# raspdancer21_1_0.net
KiCad netlist of a schematic drawn in EAGLE
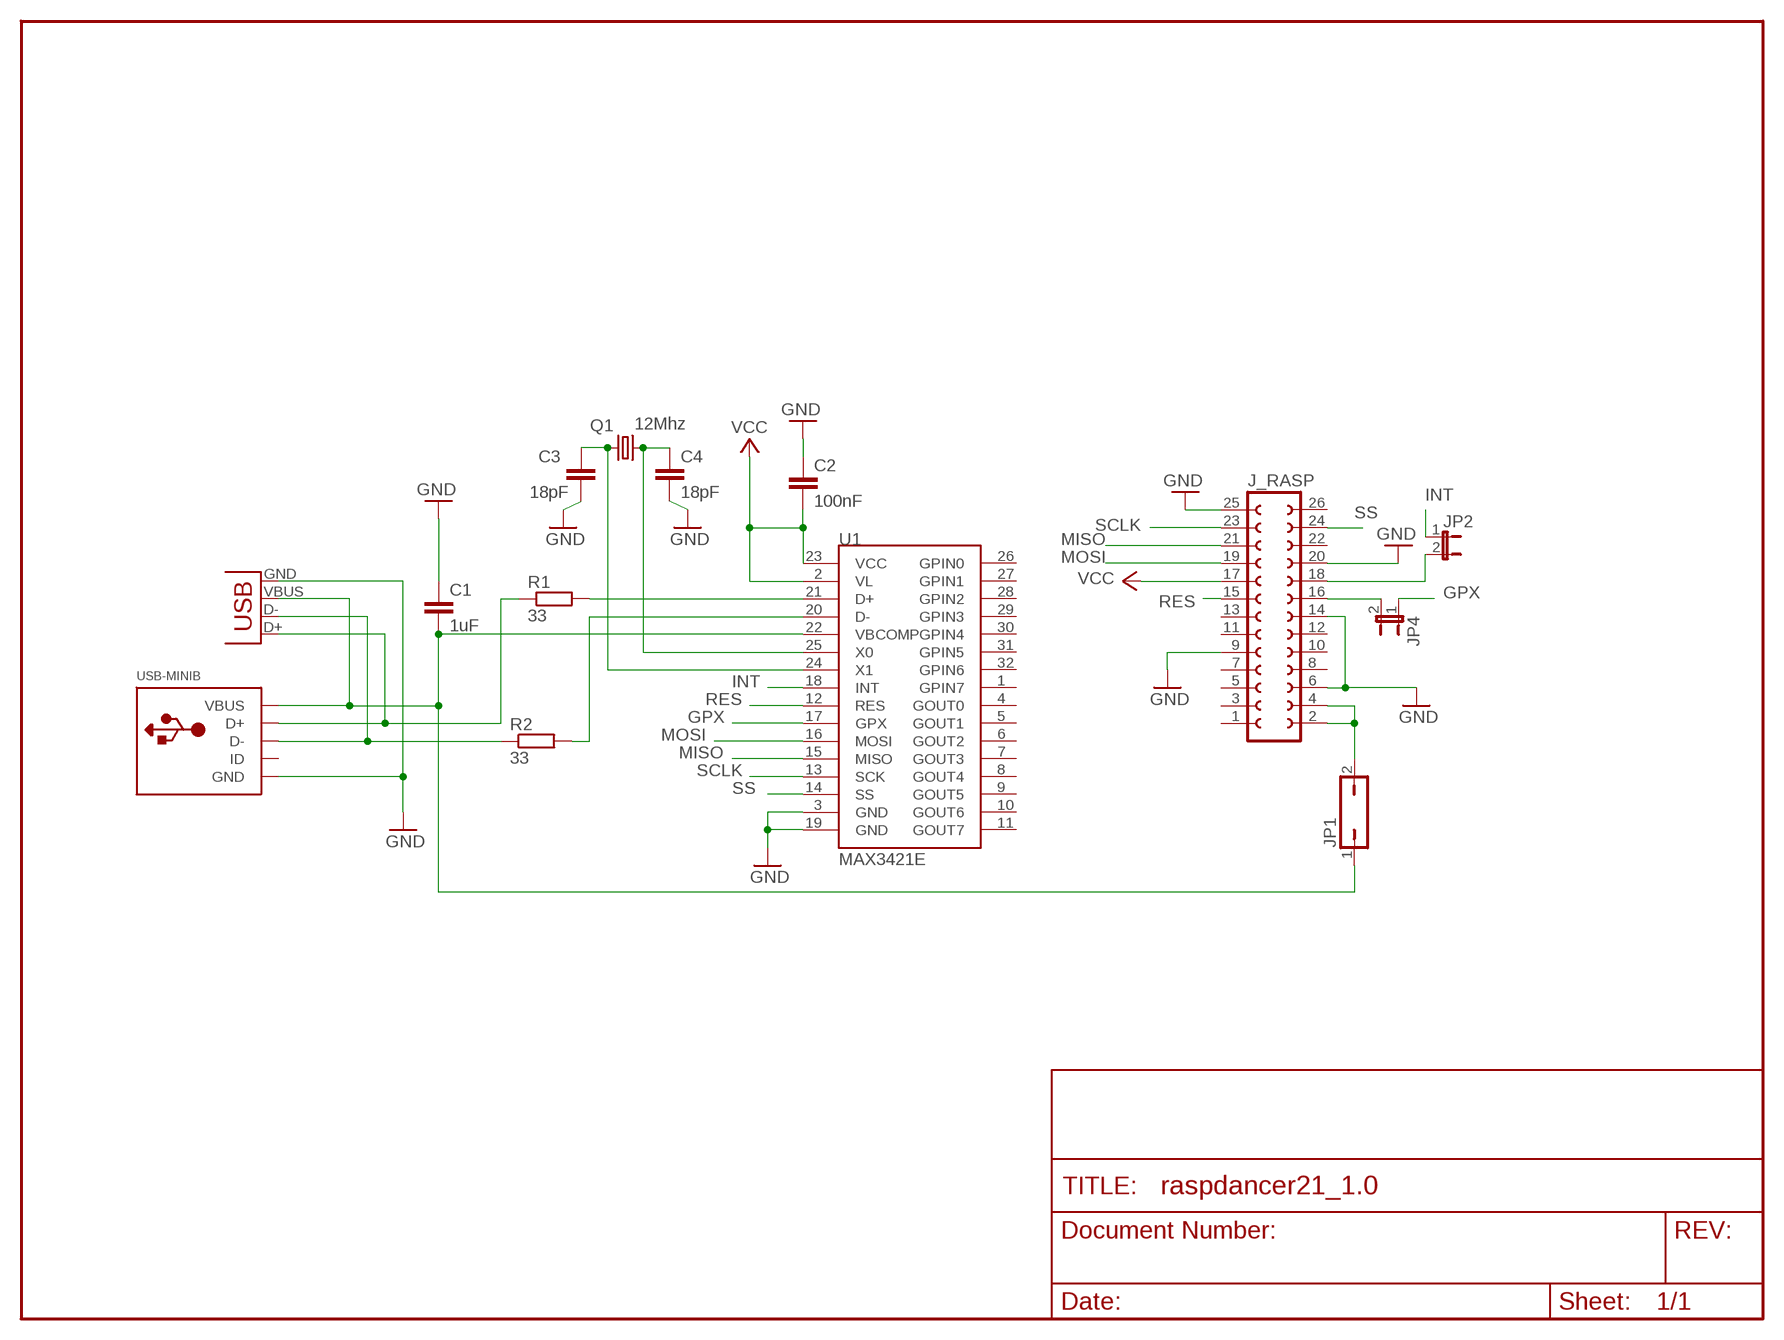
[diagram p0: schematic, sheet 1]

(export (version "E")
  (design (tool "Eeschema 10.0.6"))
  (components
    (comp (ref "C1")
      (value "1uF")
      (footprint "eagle-import:C1206")
      (libsource (lib "eagle-import") (part "C1206"))
    )
    (comp (ref "C2")
      (value "100nF")
      (footprint "eagle-import:C1206")
      (libsource (lib "eagle-import") (part "C1206"))
    )
    (comp (ref "C3")
      (value "18pF")
      (footprint "eagle-import:C1206")
      (libsource (lib "eagle-import") (part "C1206"))
    )
    (comp (ref "C4")
      (value "18pF")
      (footprint "eagle-import:C1206")
      (libsource (lib "eagle-import") (part "C1206"))
    )
    (comp (ref "JP1")
      (value "JP1Q")
      (footprint "eagle-import:JP1")
      (libsource (lib "eagle-import") (part "JP1Q"))
    )
    (comp (ref "JP2")
      (value "JUMPER-2-OLDSMD-NO")
      (footprint "eagle-import:SJ_2S-NO")
      (libsource (lib "eagle-import") (part "JUMPER-2-OLDSMD-NO"))
    )
    (comp (ref "JP4")
      (value "JUMPER-2-OLDSMD-NO")
      (footprint "eagle-import:SJ_2S-NO")
      (libsource (lib "eagle-import") (part "JUMPER-2-OLDSMD-NO"))
    )
    (comp (ref "J_RASP")
      (value "FE13-2")
      (footprint "eagle-import:FE13-2")
      (libsource (lib "eagle-import") (part "FE13-2"))
    )
    (comp (ref "Q1")
      (value "12Mhz")
      (footprint "eagle-import:CTS406")
      (libsource (lib "eagle-import") (part "CRYSTALCTS406"))
    )
    (comp (ref "R1")
      (value "33")
      (footprint "eagle-import:R1206")
      (libsource (lib "eagle-import") (part "R1206"))
    )
    (comp (ref "R2")
      (value "33")
      (footprint "eagle-import:R1206")
      (libsource (lib "eagle-import") (part "R1206"))
    )
    (comp (ref "U1")
      (value "MAX3421E")
      (footprint "eagle-import:TQFP32-5MM")
      (libsource (lib "eagle-import") (part "MAX3421ESMD"))
    )
    (comp (ref "USB-A")
      (value "USB-A-S")
      (footprint "eagle-import:USB-A-S")
      (libsource (lib "eagle-import") (part "USB-A-S"))
    )
    (comp (ref "USB-MINIB")
      (value "USBMINIB")
      (footprint "eagle-import:USB-MINIB")
      (libsource (lib "eagle-import") (part "USBMINIB"))
    )
  )
  (nets
    (net (code "1") (name "/GPX") (class "Default")
      (node (ref "JP4") (pin "1") (pinfunction "1_1") (pintype "passive"))
      (node (ref "U1") (pin "17") (pinfunction "GPX_17") (pintype "bidirectional"))
    )
    (net (code "2") (name "/INT") (class "Default")
      (node (ref "JP2") (pin "1") (pinfunction "1_1") (pintype "passive"))
      (node (ref "U1") (pin "18") (pinfunction "INT_18") (pintype "bidirectional"))
    )
    (net (code "3") (name "/MISO") (class "Default")
      (node (ref "J_RASP") (pin "21") (pinfunction "21_21") (pintype "passive"))
      (node (ref "U1") (pin "15") (pinfunction "MISO_15") (pintype "bidirectional"))
    )
    (net (code "4") (name "/MOSI") (class "Default")
      (node (ref "J_RASP") (pin "19") (pinfunction "19_19") (pintype "passive"))
      (node (ref "U1") (pin "16") (pinfunction "MOSI_16") (pintype "bidirectional"))
    )
    (net (code "5") (name "/RES") (class "Default")
      (node (ref "J_RASP") (pin "15") (pinfunction "15_15") (pintype "passive"))
      (node (ref "U1") (pin "12") (pinfunction "RES_12") (pintype "bidirectional"))
    )
    (net (code "6") (name "/SCLK") (class "Default")
      (node (ref "J_RASP") (pin "23") (pinfunction "23_23") (pintype "passive"))
      (node (ref "U1") (pin "13") (pinfunction "SCK_13") (pintype "bidirectional"))
    )
    (net (code "7") (name "/SS") (class "Default")
      (node (ref "J_RASP") (pin "24") (pinfunction "24_24") (pintype "passive"))
      (node (ref "U1") (pin "14") (pinfunction "SS_14") (pintype "bidirectional"))
    )
    (net (code "8") (name "GND") (class "Default")
      (node (ref "C1") (pin "1") (pinfunction "1_1") (pintype "passive"))
      (node (ref "C2") (pin "1") (pinfunction "1_1") (pintype "passive"))
      (node (ref "C3") (pin "2") (pinfunction "2_2") (pintype "passive"))
      (node (ref "C4") (pin "2") (pinfunction "2_2") (pintype "passive"))
      (node (ref "J_RASP") (pin "14") (pinfunction "14_14") (pintype "passive"))
      (node (ref "J_RASP") (pin "20") (pinfunction "20_20") (pintype "passive"))
      (node (ref "J_RASP") (pin "25") (pinfunction "25_25") (pintype "passive"))
      (node (ref "J_RASP") (pin "6") (pinfunction "6_6") (pintype "passive"))
      (node (ref "J_RASP") (pin "9") (pinfunction "9_9") (pintype "passive"))
      (node (ref "U1") (pin "19") (pinfunction "GND_19") (pintype "bidirectional"))
      (node (ref "U1") (pin "3") (pinfunction "GND_3") (pintype "bidirectional"))
      (node (ref "USB-A") (pin "GND") (pinfunction "GND_GND") (pintype "bidirectional"))
      (node (ref "USB-MINIB") (pin "GND") (pinfunction "GND_GND") (pintype "power_in"))
    )
    (net (code "9") (name "Net-(JP1-Pad2)") (class "Default")
      (node (ref "JP1") (pin "2") (pinfunction "2_2") (pintype "passive"))
      (node (ref "J_RASP") (pin "2") (pinfunction "2_2") (pintype "passive"))
      (node (ref "J_RASP") (pin "4") (pinfunction "4_4") (pintype "passive"))
    )
    (net (code "10") (name "Net-(JP2-Pad2)") (class "Default")
      (node (ref "JP2") (pin "2") (pinfunction "2_2") (pintype "passive"))
      (node (ref "J_RASP") (pin "18") (pinfunction "18_18") (pintype "passive"))
    )
    (net (code "11") (name "Net-(JP4-Pad2)") (class "Default")
      (node (ref "JP4") (pin "2") (pinfunction "2_2") (pintype "passive"))
      (node (ref "J_RASP") (pin "16") (pinfunction "16_16") (pintype "passive"))
    )
    (net (code "12") (name "Net-(Q1-2)") (class "Default")
      (node (ref "C4") (pin "1") (pinfunction "1_1") (pintype "passive"))
      (node (ref "Q1") (pin "3") (pinfunction "2_3") (pintype "passive"))
      (node (ref "U1") (pin "25") (pinfunction "X0_25") (pintype "bidirectional"))
    )
    (net (code "13") (name "Net-(R1-Pad1)") (class "Default")
      (node (ref "R1") (pin "1") (pinfunction "1_1") (pintype "passive"))
      (node (ref "USB-A") (pin "D+") (pinfunction "D+_D+") (pintype "bidirectional"))
      (node (ref "USB-MINIB") (pin "D+") (pinfunction "D+_D+") (pintype "bidirectional"))
    )
    (net (code "14") (name "Net-(R2-Pad1)") (class "Default")
      (node (ref "R2") (pin "1") (pinfunction "1_1") (pintype "passive"))
      (node (ref "USB-A") (pin "D-") (pinfunction "D-_D-") (pintype "bidirectional"))
      (node (ref "USB-MINIB") (pin "D-") (pinfunction "D-_D-") (pintype "bidirectional"))
    )
    (net (code "15") (name "Net-(U1-D+)") (class "Default")
      (node (ref "R1") (pin "2") (pinfunction "2_2") (pintype "passive"))
      (node (ref "U1") (pin "21") (pinfunction "D+_21") (pintype "bidirectional"))
    )
    (net (code "16") (name "Net-(U1-D-)") (class "Default")
      (node (ref "R2") (pin "2") (pinfunction "2_2") (pintype "passive"))
      (node (ref "U1") (pin "20") (pinfunction "D-_20") (pintype "bidirectional"))
    )
    (net (code "17") (name "Net-(U1-VBCOMP)") (class "Default")
      (node (ref "C1") (pin "2") (pinfunction "2_2") (pintype "passive"))
      (node (ref "JP1") (pin "1") (pinfunction "1_1") (pintype "passive"))
      (node (ref "U1") (pin "22") (pinfunction "VBCOMP_22") (pintype "bidirectional"))
      (node (ref "USB-A") (pin "VBUS") (pinfunction "VBUS_VBUS") (pintype "bidirectional"))
      (node (ref "USB-MINIB") (pin "VBUS") (pinfunction "VBUS_VBUS") (pintype "power_in"))
    )
    (net (code "18") (name "Net-(U1-X1)") (class "Default")
      (node (ref "C3") (pin "1") (pinfunction "1_1") (pintype "passive"))
      (node (ref "Q1") (pin "1") (pinfunction "1_1") (pintype "passive"))
      (node (ref "U1") (pin "24") (pinfunction "X1_24") (pintype "bidirectional"))
    )
    (net (code "19") (name "VCC") (class "Default")
      (node (ref "C2") (pin "2") (pinfunction "2_2") (pintype "passive"))
      (node (ref "J_RASP") (pin "17") (pinfunction "17_17") (pintype "passive"))
      (node (ref "U1") (pin "2") (pinfunction "VL_2") (pintype "bidirectional"))
      (node (ref "U1") (pin "23") (pinfunction "VCC_23") (pintype "bidirectional"))
    )
    (net (code "20") (name "unconnected-(J_RASP-Pad1)") (class "Default")
      (node (ref "J_RASP") (pin "1") (pinfunction "1_1") (pintype "passive"))
    )
    (net (code "21") (name "unconnected-(J_RASP-Pad3)") (class "Default")
      (node (ref "J_RASP") (pin "3") (pinfunction "3_3") (pintype "passive"))
    )
    (net (code "22") (name "unconnected-(J_RASP-Pad5)") (class "Default")
      (node (ref "J_RASP") (pin "5") (pinfunction "5_5") (pintype "passive"))
    )
    (net (code "23") (name "unconnected-(J_RASP-Pad7)") (class "Default")
      (node (ref "J_RASP") (pin "7") (pinfunction "7_7") (pintype "passive"))
    )
    (net (code "24") (name "unconnected-(J_RASP-Pad8)") (class "Default")
      (node (ref "J_RASP") (pin "8") (pinfunction "8_8") (pintype "passive"))
    )
    (net (code "25") (name "unconnected-(J_RASP-Pad10)") (class "Default")
      (node (ref "J_RASP") (pin "10") (pinfunction "10_10") (pintype "passive"))
    )
    (net (code "26") (name "unconnected-(J_RASP-Pad11)") (class "Default")
      (node (ref "J_RASP") (pin "11") (pinfunction "11_11") (pintype "passive"))
    )
    (net (code "27") (name "unconnected-(J_RASP-Pad12)") (class "Default")
      (node (ref "J_RASP") (pin "12") (pinfunction "12_12") (pintype "passive"))
    )
    (net (code "28") (name "unconnected-(J_RASP-Pad13)") (class "Default")
      (node (ref "J_RASP") (pin "13") (pinfunction "13_13") (pintype "passive"))
    )
    (net (code "29") (name "unconnected-(J_RASP-Pad22)") (class "Default")
      (node (ref "J_RASP") (pin "22") (pinfunction "22_22") (pintype "passive"))
    )
    (net (code "30") (name "unconnected-(J_RASP-Pad26)") (class "Default")
      (node (ref "J_RASP") (pin "26") (pinfunction "26_26") (pintype "passive"))
    )
    (net (code "31") (name "unconnected-(U1-GOUT0-Pad4)") (class "Default")
      (node (ref "U1") (pin "4") (pinfunction "GOUT0_4") (pintype "bidirectional"))
    )
    (net (code "32") (name "unconnected-(U1-GOUT1-Pad5)") (class "Default")
      (node (ref "U1") (pin "5") (pinfunction "GOUT1_5") (pintype "bidirectional"))
    )
    (net (code "33") (name "unconnected-(U1-GOUT2-Pad6)") (class "Default")
      (node (ref "U1") (pin "6") (pinfunction "GOUT2_6") (pintype "bidirectional"))
    )
    (net (code "34") (name "unconnected-(U1-GOUT3-Pad7)") (class "Default")
      (node (ref "U1") (pin "7") (pinfunction "GOUT3_7") (pintype "bidirectional"))
    )
    (net (code "35") (name "unconnected-(U1-GOUT4-Pad8)") (class "Default")
      (node (ref "U1") (pin "8") (pinfunction "GOUT4_8") (pintype "bidirectional"))
    )
    (net (code "36") (name "unconnected-(U1-GOUT5-Pad9)") (class "Default")
      (node (ref "U1") (pin "9") (pinfunction "GOUT5_9") (pintype "bidirectional"))
    )
    (net (code "37") (name "unconnected-(U1-GOUT6-Pad10)") (class "Default")
      (node (ref "U1") (pin "10") (pinfunction "GOUT6_10") (pintype "bidirectional"))
    )
    (net (code "38") (name "unconnected-(U1-GOUT7-Pad11)") (class "Default")
      (node (ref "U1") (pin "11") (pinfunction "GOUT7_11") (pintype "bidirectional"))
    )
    (net (code "39") (name "unconnected-(U1-GPIN0-Pad26)") (class "Default")
      (node (ref "U1") (pin "26") (pinfunction "GPIN0_26") (pintype "bidirectional"))
    )
    (net (code "40") (name "unconnected-(U1-GPIN1-Pad27)") (class "Default")
      (node (ref "U1") (pin "27") (pinfunction "GPIN1_27") (pintype "bidirectional"))
    )
    (net (code "41") (name "unconnected-(U1-GPIN2-Pad28)") (class "Default")
      (node (ref "U1") (pin "28") (pinfunction "GPIN2_28") (pintype "bidirectional"))
    )
    (net (code "42") (name "unconnected-(U1-GPIN3-Pad29)") (class "Default")
      (node (ref "U1") (pin "29") (pinfunction "GPIN3_29") (pintype "bidirectional"))
    )
    (net (code "43") (name "unconnected-(U1-GPIN4-Pad30)") (class "Default")
      (node (ref "U1") (pin "30") (pinfunction "GPIN4_30") (pintype "bidirectional"))
    )
    (net (code "44") (name "unconnected-(U1-GPIN5-Pad31)") (class "Default")
      (node (ref "U1") (pin "31") (pinfunction "GPIN5_31") (pintype "bidirectional"))
    )
    (net (code "45") (name "unconnected-(U1-GPIN6-Pad32)") (class "Default")
      (node (ref "U1") (pin "32") (pinfunction "GPIN6_32") (pintype "bidirectional"))
    )
    (net (code "46") (name "unconnected-(U1-GPIN7-Pad1)") (class "Default")
      (node (ref "U1") (pin "1") (pinfunction "GPIN7_1") (pintype "bidirectional"))
    )
    (net (code "47") (name "unconnected-(USB-MINIB-PadID)") (class "Default")
      (node (ref "USB-MINIB") (pin "ID") (pinfunction "ID_ID") (pintype "bidirectional"))
    )
  )
)
